# SFPextension.net
KiCad netlist of a schematic drawn in Altium Designer
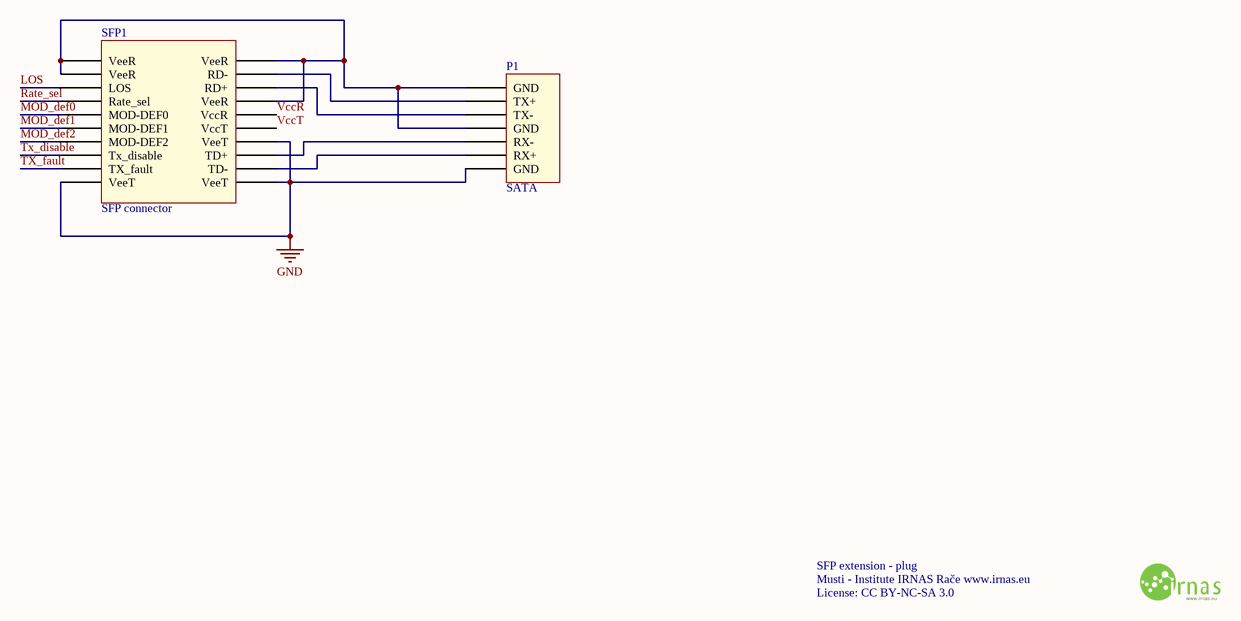
[diagram p0: SFPextension.SchDoc]

(export (version "E")
  (design (tool "Eeschema 10.0.6"))
  (components
    (comp (ref "P1")
      (value "SATA")
      (footprint "SATA pcb")
      (description "sata")
      (libsource (lib "GeneralComponents") (part "SATA"))
    )
    (comp (ref "SFP1")
      (value "SFP connector")
      (footprint "SFP pcb con")
      (libsource (lib "GeneralComponents") (part "SFP connector"))
    )
  )
  (nets
    (net (code "1") (name "/LOS") (class "Default")
      (node (ref "SFP1") (pin "8") (pinfunction "LOS_8") (pintype "power_in"))
    )
    (net (code "2") (name "/MOD_def0") (class "Default")
      (node (ref "SFP1") (pin "6") (pinfunction "MOD-DEF0_6") (pintype "power_in"))
    )
    (net (code "3") (name "/MOD_def1") (class "Default")
      (node (ref "SFP1") (pin "5") (pinfunction "MOD-DEF1_5") (pintype "power_in"))
    )
    (net (code "4") (name "/MOD_def2") (class "Default")
      (node (ref "SFP1") (pin "4") (pinfunction "MOD-DEF2_4") (pintype "power_in"))
    )
    (net (code "5") (name "/Rate_sel") (class "Default")
      (node (ref "SFP1") (pin "7") (pinfunction "Rate_sel_7") (pintype "power_in"))
    )
    (net (code "6") (name "/TX_fault") (class "Default")
      (node (ref "SFP1") (pin "2") (pinfunction "TX_fault_2") (pintype "power_in"))
    )
    (net (code "7") (name "/Tx_disable") (class "Default")
      (node (ref "SFP1") (pin "3") (pinfunction "Tx_disable_3") (pintype "power_in"))
    )
    (net (code "8") (name "/VccR") (class "Default")
      (node (ref "SFP1") (pin "15") (pinfunction "VccR_15") (pintype "power_in"))
    )
    (net (code "9") (name "/VccT") (class "Default")
      (node (ref "SFP1") (pin "16") (pinfunction "VccT_16") (pintype "power_in"))
    )
    (net (code "10") (name "GND") (class "Default")
      (node (ref "P1") (pin "7") (pinfunction "GND_7") (pintype "power_in"))
      (node (ref "SFP1") (pin "1") (pinfunction "VeeT_1") (pintype "power_in"))
      (node (ref "SFP1") (pin "17") (pinfunction "VeeT_17") (pintype "power_in"))
      (node (ref "SFP1") (pin "20") (pinfunction "VeeT_20") (pintype "power_in"))
    )
    (net (code "11") (name "Net-(P1-GND-Pad1)") (class "Default")
      (node (ref "P1") (pin "1") (pinfunction "GND_1") (pintype "power_in"))
      (node (ref "P1") (pin "4") (pinfunction "GND_4") (pintype "power_in"))
      (node (ref "SFP1") (pin "10") (pinfunction "VeeR_10") (pintype "power_in"))
      (node (ref "SFP1") (pin "11") (pinfunction "VeeR_11") (pintype "power_in"))
      (node (ref "SFP1") (pin "14") (pinfunction "VeeR_14") (pintype "power_in"))
      (node (ref "SFP1") (pin "9") (pinfunction "VeeR_9") (pintype "power_in"))
    )
    (net (code "12") (name "Net-(P1-RX+)") (class "Default")
      (node (ref "P1") (pin "6") (pinfunction "RX+_6") (pintype "power_in"))
      (node (ref "SFP1") (pin "19") (pinfunction "TD-_19") (pintype "power_in"))
    )
    (net (code "13") (name "Net-(P1-RX-)") (class "Default")
      (node (ref "P1") (pin "5") (pinfunction "RX-_5") (pintype "power_in"))
      (node (ref "SFP1") (pin "18") (pinfunction "TD+_18") (pintype "power_in"))
    )
    (net (code "14") (name "Net-(P1-TX+)") (class "Default")
      (node (ref "P1") (pin "2") (pinfunction "TX+_2") (pintype "power_in"))
      (node (ref "SFP1") (pin "12") (pinfunction "RD-_12") (pintype "power_in"))
    )
    (net (code "15") (name "Net-(P1-TX-)") (class "Default")
      (node (ref "P1") (pin "3") (pinfunction "TX-_3") (pintype "power_in"))
      (node (ref "SFP1") (pin "13") (pinfunction "RD+_13") (pintype "power_in"))
    )
  )
)
